# 8_imu_debug_conn.net
KiCad netlist of a schematic drawn in Altium Designer
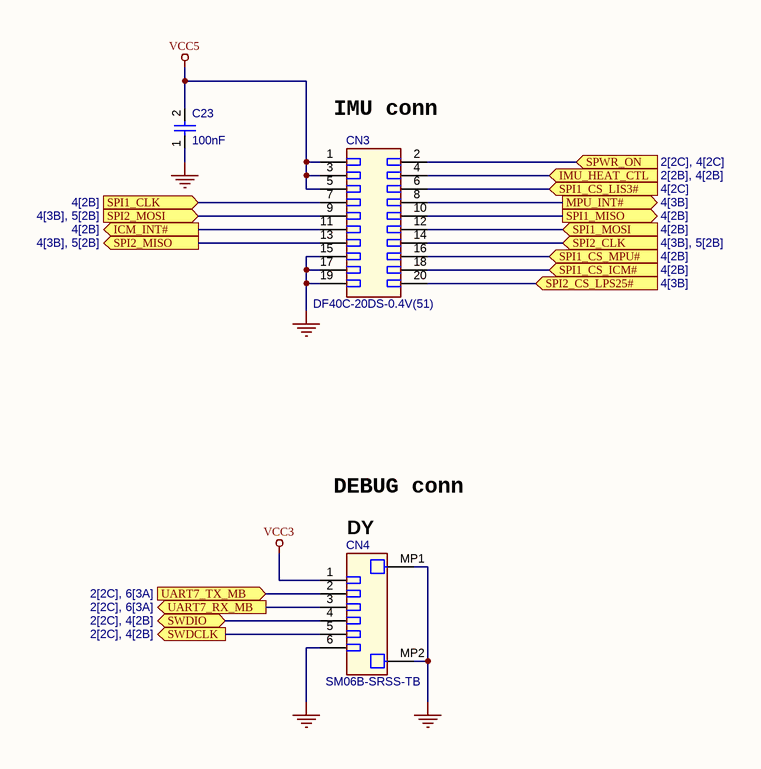
[diagram p0: 8_imu&debug_conn.SchDoc]

(export (version "E")
  (design (tool "Eeschema 10.0.6"))
  (components
    (comp (ref "C23")
      (value "100nF")
      (footprint "CAPC0402(1005)60_L")
      (description "Chip Capacitor, 100nF +/-20%, 10V, 0402, Thickness 0.6 mm")
      (fields (field (name "TOLERANCE") "20%") (field (name "Comment") "Capacitor 100nF +/-20% 10V 0402"))
      (libsource (lib "<Company> Server") (part "CAP-NP-2"))
    )
    (comp (ref "CN3")
      (value "DF40C-20DS-0.4V(51)")
      (footprint "HIRO-DF40C-20DS-0.4V(51)_V")
      (description "Receptacle Connector, 30 V, 0.3 A, -35 to 85 degC, RoHS, Tape and Reel")
      (libsource (lib "<Company> Server") (part "CMP-00114-7"))
    )
    (comp (ref "CN4")
      (value "SM06B-SRSS-TB")
      (footprint "JST-SM06B-SRSS-TB_V")
      (description "Male Header, Pitch 1 mm, 1 x 6 Position, Height 2.95 mm, -25 to 85 degC, RoHS, Tape and Reel")
      (libsource (lib "<Company> Server") (part "CMP-00143-5"))
    )
  )
  (nets
    (net (code "1") (name "/ICM_INT#") (class "Default")
      (node (ref "CN3") (pin "11") (pinfunction "11_11") (pintype "passive"))
    )
    (net (code "2") (name "/IMU_HEAT_CTL") (class "Default")
      (node (ref "CN3") (pin "4") (pinfunction "4_4") (pintype "passive"))
    )
    (net (code "3") (name "/MPU_INT#") (class "Default")
      (node (ref "CN3") (pin "8") (pinfunction "8_8") (pintype "passive"))
    )
    (net (code "4") (name "/SPI1_CLK") (class "Default")
      (node (ref "CN3") (pin "7") (pinfunction "7_7") (pintype "passive"))
    )
    (net (code "5") (name "/SPI1_CS_ICM#") (class "Default")
      (node (ref "CN3") (pin "18") (pinfunction "18_18") (pintype "passive"))
    )
    (net (code "6") (name "/SPI1_CS_LIS3#") (class "Default")
      (node (ref "CN3") (pin "6") (pinfunction "6_6") (pintype "passive"))
    )
    (net (code "7") (name "/SPI1_CS_MPU#") (class "Default")
      (node (ref "CN3") (pin "16") (pinfunction "16_16") (pintype "passive"))
    )
    (net (code "8") (name "/SPI1_MISO") (class "Default")
      (node (ref "CN3") (pin "10") (pinfunction "10_10") (pintype "passive"))
    )
    (net (code "9") (name "/SPI1_MOSI") (class "Default")
      (node (ref "CN3") (pin "12") (pinfunction "12_12") (pintype "passive"))
    )
    (net (code "10") (name "/SPI2_CLK") (class "Default")
      (node (ref "CN3") (pin "14") (pinfunction "14_14") (pintype "passive"))
    )
    (net (code "11") (name "/SPI2_CS_LPS25#") (class "Default")
      (node (ref "CN3") (pin "20") (pinfunction "20_20") (pintype "passive"))
    )
    (net (code "12") (name "/SPI2_MISO") (class "Default")
      (node (ref "CN3") (pin "13") (pinfunction "13_13") (pintype "passive"))
    )
    (net (code "13") (name "/SPI2_MOSI") (class "Default")
      (node (ref "CN3") (pin "9") (pinfunction "9_9") (pintype "passive"))
    )
    (net (code "14") (name "/SPWR_ON") (class "Default")
      (node (ref "CN3") (pin "2") (pinfunction "2_2") (pintype "passive"))
    )
    (net (code "15") (name "/SWDCLK") (class "Default")
      (node (ref "CN4") (pin "5") (pinfunction "5_5") (pintype "passive"))
    )
    (net (code "16") (name "/SWDIO") (class "Default")
      (node (ref "CN4") (pin "4") (pinfunction "4_4") (pintype "passive"))
    )
    (net (code "17") (name "/UART7_RX_MB") (class "Default")
      (node (ref "CN4") (pin "3") (pinfunction "3_3") (pintype "passive"))
    )
    (net (code "18") (name "/UART7_TX_MB") (class "Default")
      (node (ref "CN4") (pin "2") (pinfunction "2_2") (pintype "passive"))
    )
    (net (code "19") (name "GND") (class "Default")
      (node (ref "C23") (pin "1") (pinfunction "1_1") (pintype "passive"))
      (node (ref "CN3") (pin "15") (pinfunction "15_15") (pintype "passive"))
      (node (ref "CN3") (pin "17") (pinfunction "17_17") (pintype "passive"))
      (node (ref "CN3") (pin "19") (pinfunction "19_19") (pintype "passive"))
      (node (ref "CN4") (pin "6") (pinfunction "6_6") (pintype "passive"))
      (node (ref "CN4") (pin "MP1") (pinfunction "MP1_MP1") (pintype "passive"))
      (node (ref "CN4") (pin "MP2") (pinfunction "MP2_MP2") (pintype "passive"))
    )
    (net (code "20") (name "VCC3") (class "Default")
      (node (ref "CN4") (pin "1") (pinfunction "1_1") (pintype "passive"))
    )
    (net (code "21") (name "VCC5") (class "Default")
      (node (ref "C23") (pin "2") (pinfunction "2_2") (pintype "passive"))
      (node (ref "CN3") (pin "1") (pinfunction "1_1") (pintype "passive"))
      (node (ref "CN3") (pin "3") (pinfunction "3_3") (pintype "passive"))
      (node (ref "CN3") (pin "5") (pinfunction "5_5") (pintype "passive"))
    )
  )
)
